# HABSat2_schematic.net
KiCad netlist of a schematic drawn in EasyEDA
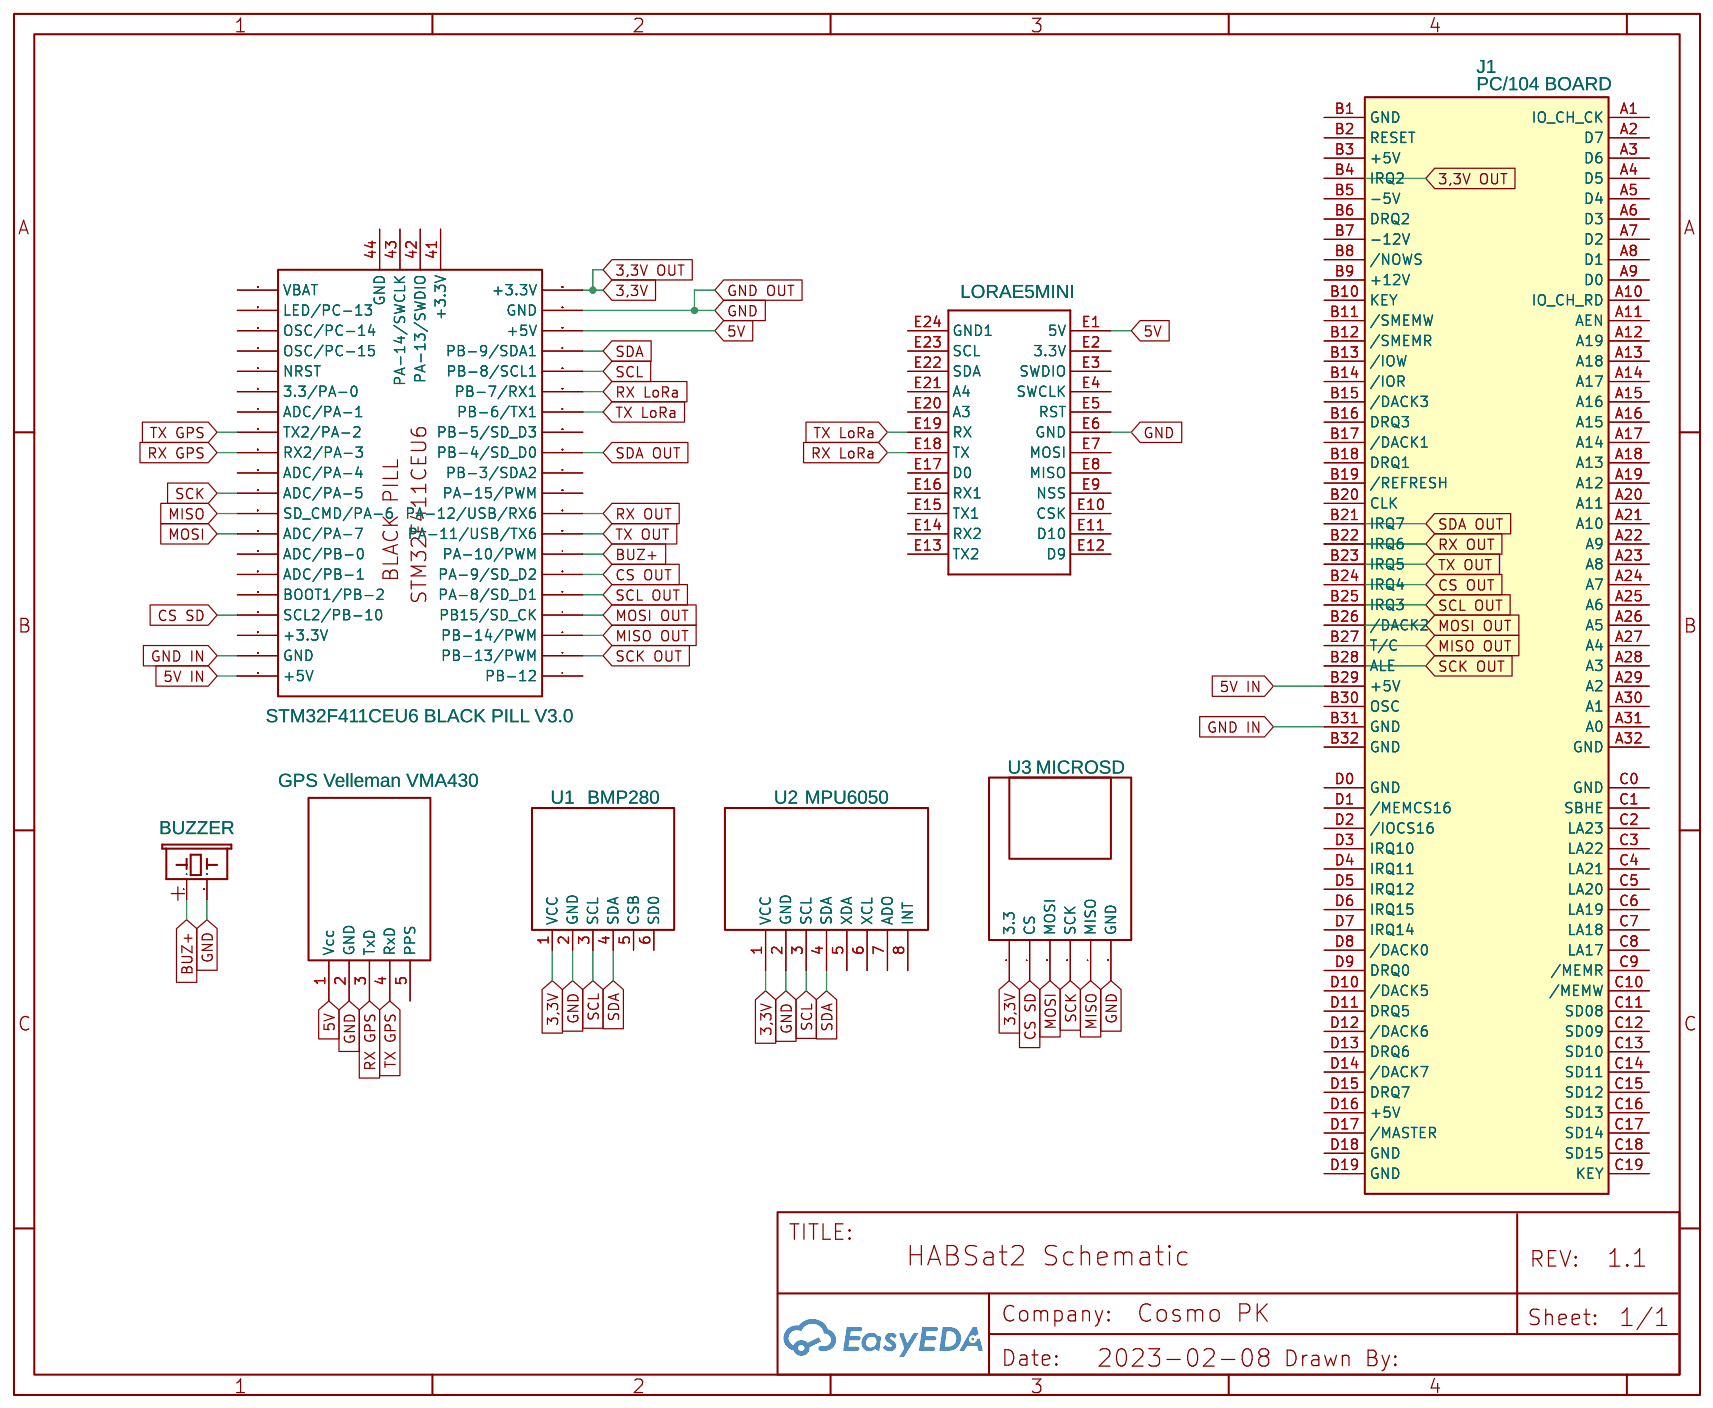
[diagram p0: schematic sheet]

(export (version "E")
  (design (tool "Eeschema 10.0.6"))
  (components
    (comp (ref "1") (value "LORAE5MINI") (libsource (lib "") (part "LORAE5MINI")))
    (comp (ref "J1") (value "PC/104 BOARD") (libsource (lib "") (part "PC/104 BOARD")))
    (comp (ref "SG1") (value "BUZZER") (libsource (lib "") (part "BUZZER KX-12MM")))
    (comp (ref "STM1")
      (value "STM32F411CEU6 BLACK PILL V3.0")
      (libsource (lib "") (part "STM32F411CEU6 BLACK PILL V3.0"))
    )
    (comp (ref "U1")
      (value "BMP280")
      (fields (field (name "BOM_Manufacturer Part") "GY-BMP280"))
      (libsource (lib "") (part "GY-BMP280"))
    )
    (comp (ref "U2") (value "MPU6050") (libsource (lib "") (part "MPU6050")))
    (comp (ref "U3") (value "MICROSD") (libsource (lib "") (part "MICROSD")))
    (comp (ref "VCC")
      (value "GPS Velleman VMA430")
      (fields (field (name "BOM_Manufacturer Part") "VMA430"))
      (libsource (lib "") (part "GPS Velleman VMA430"))
    )
  )
  (nets
    (net (code "1") (name "3,3V") (class "Default")
      (node (ref "J1") (pin "B4") (pinfunction "IRQ2_B4") (pintype "unspecified"))
      (node (ref "STM1") (pin "20") (pinfunction "+3.3V_20") (pintype "unspecified"))
      (node (ref "U1") (pin "1") (pinfunction "VCC_1") (pintype "unspecified"))
      (node (ref "U2") (pin "1") (pinfunction "VCC_1") (pintype "unspecified"))
      (node (ref "U3") (pin "5") (pinfunction "3.3_5") (pintype "unspecified"))
    )
    (net (code "2") (name "5V") (class "Default")
      (node (ref "1") (pin "E1") (pinfunction "5V_E1") (pintype "bidirectional"))
      (node (ref "STM1") (pin "18") (pinfunction "+5V_18") (pintype "unspecified"))
      (node (ref "VCC") (pin "1") (pinfunction "Vcc_1") (pintype "unspecified"))
    )
    (net (code "3") (name "5V IN") (class "Default")
      (node (ref "J1") (pin "B29") (pinfunction "+5V_B29") (pintype "bidirectional"))
      (node (ref "STM1") (pin "40") (pinfunction "+5V_40") (pintype "unspecified"))
    )
    (net (code "4") (name "BUZ+") (class "Default")
      (node (ref "SG1") (pin "1") (pinfunction "1_1") (pintype "unspecified"))
      (node (ref "STM1") (pin "7") (pinfunction "PA-10/PWM_7") (pintype "unspecified"))
    )
    (net (code "5") (name "CS OUT") (class "Default")
      (node (ref "J1") (pin "B24") (pinfunction "IRQ4_B24") (pintype "unspecified"))
      (node (ref "STM1") (pin "6") (pinfunction "PA-9/SD_D2_6") (pintype "unspecified"))
    )
    (net (code "6") (name "CS SD") (class "Default")
      (node (ref "STM1") (pin "37") (pinfunction "SCL2/PB-10_37") (pintype "unspecified"))
      (node (ref "U3") (pin "1") (pinfunction "CS_1") (pintype "unspecified"))
    )
    (net (code "7") (name "GND") (class "Default")
      (node (ref "1") (pin "E6") (pinfunction "GND_E6") (pintype "bidirectional"))
      (node (ref "SG1") (pin "2") (pinfunction "2_2") (pintype "unspecified"))
      (node (ref "STM1") (pin "19") (pinfunction "GND_19") (pintype "unspecified"))
      (node (ref "U1") (pin "2") (pinfunction "GND_2") (pintype "unspecified"))
      (node (ref "U2") (pin "2") (pinfunction "GND_2") (pintype "unspecified"))
      (node (ref "U3") (pin "6") (pinfunction "GND_6") (pintype "unspecified"))
      (node (ref "VCC") (pin "2") (pinfunction "GND_2") (pintype "unspecified"))
    )
    (net (code "8") (name "GND IN") (class "Default")
      (node (ref "J1") (pin "B31") (pinfunction "GND_B31") (pintype "bidirectional"))
      (node (ref "STM1") (pin "39") (pinfunction "GND_39") (pintype "unspecified"))
    )
    (net (code "9") (name "MISO") (class "Default")
      (node (ref "STM1") (pin "32") (pinfunction "SD_CMD/PA-6_32") (pintype "unspecified"))
      (node (ref "U3") (pin "4") (pinfunction "MISO_4") (pintype "unspecified"))
    )
    (net (code "10") (name "MISO OUT") (class "Default")
      (node (ref "J1") (pin "B27") (pinfunction "T/C_B27") (pintype "unspecified"))
      (node (ref "STM1") (pin "3") (pinfunction "PB-14/PWM_3") (pintype "unspecified"))
    )
    (net (code "11") (name "MOSI") (class "Default")
      (node (ref "STM1") (pin "33") (pinfunction "ADC/PA-7_33") (pintype "unspecified"))
      (node (ref "U3") (pin "3") (pinfunction "MOSI_3") (pintype "unspecified"))
    )
    (net (code "12") (name "MOSI OUT") (class "Default")
      (node (ref "J1") (pin "B26") (pinfunction "/DACK2_B26") (pintype "unspecified"))
      (node (ref "STM1") (pin "4") (pinfunction "PB15/SD_CK_4") (pintype "unspecified"))
    )
    (net (code "13") (name "RX GPS") (class "Default")
      (node (ref "STM1") (pin "29") (pinfunction "RX2/PA-3_29") (pintype "unspecified"))
      (node (ref "VCC") (pin "3") (pinfunction "TxD_3") (pintype "unspecified"))
    )
    (net (code "14") (name "RX LoRa") (class "Default")
      (node (ref "1") (pin "E18") (pinfunction "TX_E18") (pintype "bidirectional"))
      (node (ref "STM1") (pin "15") (pinfunction "PB-7/RX1_15") (pintype "unspecified"))
    )
    (net (code "15") (name "RX OUT") (class "Default")
      (node (ref "J1") (pin "B22") (pinfunction "IRQ6_B22") (pintype "unspecified"))
      (node (ref "STM1") (pin "9") (pinfunction "PA-12/USB/RX6_9") (pintype "unspecified"))
    )
    (net (code "16") (name "SCK") (class "Default")
      (node (ref "STM1") (pin "31") (pinfunction "ADC/PA-5_31") (pintype "unspecified"))
      (node (ref "U3") (pin "2") (pinfunction "SCK_2") (pintype "unspecified"))
    )
    (net (code "17") (name "SCK OUT") (class "Default")
      (node (ref "J1") (pin "B28") (pinfunction "ALE_B28") (pintype "output"))
      (node (ref "STM1") (pin "2") (pinfunction "PB-13/PWM_2") (pintype "unspecified"))
    )
    (net (code "18") (name "SCL") (class "Default")
      (node (ref "STM1") (pin "16") (pinfunction "PB-8/SCL1_16") (pintype "unspecified"))
      (node (ref "U1") (pin "3") (pinfunction "SCL_3") (pintype "unspecified"))
      (node (ref "U2") (pin "3") (pinfunction "SCL_3") (pintype "unspecified"))
    )
    (net (code "19") (name "SCL OUT") (class "Default")
      (node (ref "J1") (pin "B25") (pinfunction "IRQ3_B25") (pintype "unspecified"))
      (node (ref "STM1") (pin "5") (pinfunction "PA-8/SD_D1_5") (pintype "unspecified"))
    )
    (net (code "20") (name "SDA") (class "Default")
      (node (ref "STM1") (pin "17") (pinfunction "PB-9/SDA1_17") (pintype "unspecified"))
      (node (ref "U1") (pin "4") (pinfunction "SDA_4") (pintype "unspecified"))
      (node (ref "U2") (pin "4") (pinfunction "SDA_4") (pintype "unspecified"))
    )
    (net (code "21") (name "SDA OUT") (class "Default")
      (node (ref "J1") (pin "B21") (pinfunction "IRQ7_B21") (pintype "unspecified"))
      (node (ref "STM1") (pin "12") (pinfunction "PB-4/SD_D0_12") (pintype "unspecified"))
    )
    (net (code "22") (name "TX GPS") (class "Default")
      (node (ref "STM1") (pin "28") (pinfunction "TX2/PA-2_28") (pintype "unspecified"))
      (node (ref "VCC") (pin "4") (pinfunction "RxD_4") (pintype "unspecified"))
    )
    (net (code "23") (name "TX LoRa") (class "Default")
      (node (ref "1") (pin "E19") (pinfunction "RX_E19") (pintype "bidirectional"))
      (node (ref "STM1") (pin "14") (pinfunction "PB-6/TX1_14") (pintype "unspecified"))
    )
    (net (code "24") (name "TX OUT") (class "Default")
      (node (ref "J1") (pin "B23") (pinfunction "IRQ5_B23") (pintype "unspecified"))
      (node (ref "STM1") (pin "8") (pinfunction "PA-11/USB/TX6_8") (pintype "unspecified"))
    )
    (net (code "25") (name "unconnected-(1-3.3V-PadE2)") (class "Default")
      (node (ref "1") (pin "E2") (pinfunction "3.3V_E2") (pintype "bidirectional"))
    )
    (net (code "26") (name "unconnected-(1-A3-PadE20)") (class "Default")
      (node (ref "1") (pin "E20") (pinfunction "A3_E20") (pintype "bidirectional"))
    )
    (net (code "27") (name "unconnected-(1-A4-PadE21)") (class "Default")
      (node (ref "1") (pin "E21") (pinfunction "A4_E21") (pintype "bidirectional"))
    )
    (net (code "28") (name "unconnected-(1-CSK-PadE10)") (class "Default")
      (node (ref "1") (pin "E10") (pinfunction "CSK_E10") (pintype "bidirectional"))
    )
    (net (code "29") (name "unconnected-(1-D0-PadE17)") (class "Default")
      (node (ref "1") (pin "E17") (pinfunction "D0_E17") (pintype "bidirectional"))
    )
    (net (code "30") (name "unconnected-(1-D9-PadE12)") (class "Default")
      (node (ref "1") (pin "E12") (pinfunction "D9_E12") (pintype "bidirectional"))
    )
    (net (code "31") (name "unconnected-(1-D10-PadE11)") (class "Default")
      (node (ref "1") (pin "E11") (pinfunction "D10_E11") (pintype "bidirectional"))
    )
    (net (code "32") (name "unconnected-(1-GND1-PadE24)") (class "Default")
      (node (ref "1") (pin "E24") (pinfunction "GND1_E24") (pintype "bidirectional"))
    )
    (net (code "33") (name "unconnected-(1-MISO-PadE8)") (class "Default")
      (node (ref "1") (pin "E8") (pinfunction "MISO_E8") (pintype "bidirectional"))
    )
    (net (code "34") (name "unconnected-(1-MOSI-PadE7)") (class "Default")
      (node (ref "1") (pin "E7") (pinfunction "MOSI_E7") (pintype "bidirectional"))
    )
    (net (code "35") (name "unconnected-(1-NSS-PadE9)") (class "Default")
      (node (ref "1") (pin "E9") (pinfunction "NSS_E9") (pintype "bidirectional"))
    )
    (net (code "36") (name "unconnected-(1-RST-PadE5)") (class "Default")
      (node (ref "1") (pin "E5") (pinfunction "RST_E5") (pintype "bidirectional"))
    )
    (net (code "37") (name "unconnected-(1-RX1-PadE16)") (class "Default")
      (node (ref "1") (pin "E16") (pinfunction "RX1_E16") (pintype "bidirectional"))
    )
    (net (code "38") (name "unconnected-(1-RX2-PadE14)") (class "Default")
      (node (ref "1") (pin "E14") (pinfunction "RX2_E14") (pintype "bidirectional"))
    )
    (net (code "39") (name "unconnected-(1-SCL-PadE23)") (class "Default")
      (node (ref "1") (pin "E23") (pinfunction "SCL_E23") (pintype "bidirectional"))
    )
    (net (code "40") (name "unconnected-(1-SDA-PadE22)") (class "Default")
      (node (ref "1") (pin "E22") (pinfunction "SDA_E22") (pintype "bidirectional"))
    )
    (net (code "41") (name "unconnected-(1-SWCLK-PadE4)") (class "Default")
      (node (ref "1") (pin "E4") (pinfunction "SWCLK_E4") (pintype "bidirectional"))
    )
    (net (code "42") (name "unconnected-(1-SWDIO-PadE3)") (class "Default")
      (node (ref "1") (pin "E3") (pinfunction "SWDIO_E3") (pintype "bidirectional"))
    )
    (net (code "43") (name "unconnected-(1-TX1-PadE15)") (class "Default")
      (node (ref "1") (pin "E15") (pinfunction "TX1_E15") (pintype "bidirectional"))
    )
    (net (code "44") (name "unconnected-(1-TX2-PadE13)") (class "Default")
      (node (ref "1") (pin "E13") (pinfunction "TX2_E13") (pintype "bidirectional"))
    )
    (net (code "45") (name "unconnected-(J1-+5V-PadB3)") (class "Default")
      (node (ref "J1") (pin "B3") (pinfunction "+5V_B3") (pintype "bidirectional"))
    )
    (net (code "46") (name "unconnected-(J1-+5V-PadD16)") (class "Default")
      (node (ref "J1") (pin "D16") (pinfunction "+5V_D16") (pintype "bidirectional"))
    )
    (net (code "47") (name "unconnected-(J1-+12V-PadB9)") (class "Default")
      (node (ref "J1") (pin "B9") (pinfunction "+12V_B9") (pintype "bidirectional"))
    )
    (net (code "48") (name "unconnected-(J1--5V-PadB5)") (class "Default")
      (node (ref "J1") (pin "B5") (pinfunction "-5V_B5") (pintype "bidirectional"))
    )
    (net (code "49") (name "unconnected-(J1--12V-PadB7)") (class "Default")
      (node (ref "J1") (pin "B7") (pinfunction "-12V_B7") (pintype "bidirectional"))
    )
    (net (code "50") (name "unconnected-(J1-A0-PadA31)") (class "Default")
      (node (ref "J1") (pin "A31") (pinfunction "A0_A31") (pintype "bidirectional"))
    )
    (net (code "51") (name "unconnected-(J1-A1-PadA30)") (class "Default")
      (node (ref "J1") (pin "A30") (pinfunction "A1_A30") (pintype "bidirectional"))
    )
    (net (code "52") (name "unconnected-(J1-A2-PadA29)") (class "Default")
      (node (ref "J1") (pin "A29") (pinfunction "A2_A29") (pintype "bidirectional"))
    )
    (net (code "53") (name "unconnected-(J1-A3-PadA28)") (class "Default")
      (node (ref "J1") (pin "A28") (pinfunction "A3_A28") (pintype "bidirectional"))
    )
    (net (code "54") (name "unconnected-(J1-A4-PadA27)") (class "Default")
      (node (ref "J1") (pin "A27") (pinfunction "A4_A27") (pintype "bidirectional"))
    )
    (net (code "55") (name "unconnected-(J1-A5-PadA26)") (class "Default")
      (node (ref "J1") (pin "A26") (pinfunction "A5_A26") (pintype "bidirectional"))
    )
    (net (code "56") (name "unconnected-(J1-A6-PadA25)") (class "Default")
      (node (ref "J1") (pin "A25") (pinfunction "A6_A25") (pintype "bidirectional"))
    )
    (net (code "57") (name "unconnected-(J1-A7-PadA24)") (class "Default")
      (node (ref "J1") (pin "A24") (pinfunction "A7_A24") (pintype "bidirectional"))
    )
    (net (code "58") (name "unconnected-(J1-A8-PadA23)") (class "Default")
      (node (ref "J1") (pin "A23") (pinfunction "A8_A23") (pintype "bidirectional"))
    )
    (net (code "59") (name "unconnected-(J1-A9-PadA22)") (class "Default")
      (node (ref "J1") (pin "A22") (pinfunction "A9_A22") (pintype "bidirectional"))
    )
    (net (code "60") (name "unconnected-(J1-A10-PadA21)") (class "Default")
      (node (ref "J1") (pin "A21") (pinfunction "A10_A21") (pintype "bidirectional"))
    )
    (net (code "61") (name "unconnected-(J1-A11-PadA20)") (class "Default")
      (node (ref "J1") (pin "A20") (pinfunction "A11_A20") (pintype "bidirectional"))
    )
    (net (code "62") (name "unconnected-(J1-A12-PadA19)") (class "Default")
      (node (ref "J1") (pin "A19") (pinfunction "A12_A19") (pintype "bidirectional"))
    )
    (net (code "63") (name "unconnected-(J1-A13-PadA18)") (class "Default")
      (node (ref "J1") (pin "A18") (pinfunction "A13_A18") (pintype "bidirectional"))
    )
    (net (code "64") (name "unconnected-(J1-A14-PadA17)") (class "Default")
      (node (ref "J1") (pin "A17") (pinfunction "A14_A17") (pintype "bidirectional"))
    )
    (net (code "65") (name "unconnected-(J1-A15-PadA16)") (class "Default")
      (node (ref "J1") (pin "A16") (pinfunction "A15_A16") (pintype "bidirectional"))
    )
    (net (code "66") (name "unconnected-(J1-A16-PadA15)") (class "Default")
      (node (ref "J1") (pin "A15") (pinfunction "A16_A15") (pintype "bidirectional"))
    )
    (net (code "67") (name "unconnected-(J1-A17-PadA14)") (class "Default")
      (node (ref "J1") (pin "A14") (pinfunction "A17_A14") (pintype "bidirectional"))
    )
    (net (code "68") (name "unconnected-(J1-A18-PadA13)") (class "Default")
      (node (ref "J1") (pin "A13") (pinfunction "A18_A13") (pintype "bidirectional"))
    )
    (net (code "69") (name "unconnected-(J1-A19-PadA12)") (class "Default")
      (node (ref "J1") (pin "A12") (pinfunction "A19_A12") (pintype "bidirectional"))
    )
    (net (code "70") (name "unconnected-(J1-AEN-PadA11)") (class "Default")
      (node (ref "J1") (pin "A11") (pinfunction "AEN_A11") (pintype "output"))
    )
    (net (code "71") (name "unconnected-(J1-CLK-PadB20)") (class "Default")
      (node (ref "J1") (pin "B20") (pinfunction "CLK_B20") (pintype "output"))
    )
    (net (code "72") (name "unconnected-(J1-D0-PadA9)") (class "Default")
      (node (ref "J1") (pin "A9") (pinfunction "D0_A9") (pintype "bidirectional"))
    )
    (net (code "73") (name "unconnected-(J1-D1-PadA8)") (class "Default")
      (node (ref "J1") (pin "A8") (pinfunction "D1_A8") (pintype "bidirectional"))
    )
    (net (code "74") (name "unconnected-(J1-D2-PadA7)") (class "Default")
      (node (ref "J1") (pin "A7") (pinfunction "D2_A7") (pintype "bidirectional"))
    )
    (net (code "75") (name "unconnected-(J1-D3-PadA6)") (class "Default")
      (node (ref "J1") (pin "A6") (pinfunction "D3_A6") (pintype "bidirectional"))
    )
    (net (code "76") (name "unconnected-(J1-D4-PadA5)") (class "Default")
      (node (ref "J1") (pin "A5") (pinfunction "D4_A5") (pintype "bidirectional"))
    )
    (net (code "77") (name "unconnected-(J1-D5-PadA4)") (class "Default")
      (node (ref "J1") (pin "A4") (pinfunction "D5_A4") (pintype "bidirectional"))
    )
    (net (code "78") (name "unconnected-(J1-D6-PadA3)") (class "Default")
      (node (ref "J1") (pin "A3") (pinfunction "D6_A3") (pintype "bidirectional"))
    )
    (net (code "79") (name "unconnected-(J1-D7-PadA2)") (class "Default")
      (node (ref "J1") (pin "A2") (pinfunction "D7_A2") (pintype "bidirectional"))
    )
    (net (code "80") (name "unconnected-(J1-DRQ0-PadD9)") (class "Default")
      (node (ref "J1") (pin "D9") (pinfunction "DRQ0_D9") (pintype "unspecified"))
    )
    (net (code "81") (name "unconnected-(J1-DRQ1-PadB18)") (class "Default")
      (node (ref "J1") (pin "B18") (pinfunction "DRQ1_B18") (pintype "unspecified"))
    )
    (net (code "82") (name "unconnected-(J1-DRQ2-PadB6)") (class "Default")
      (node (ref "J1") (pin "B6") (pinfunction "DRQ2_B6") (pintype "unspecified"))
    )
    (net (code "83") (name "unconnected-(J1-DRQ3-PadB16)") (class "Default")
      (node (ref "J1") (pin "B16") (pinfunction "DRQ3_B16") (pintype "unspecified"))
    )
    (net (code "84") (name "unconnected-(J1-DRQ5-PadD11)") (class "Default")
      (node (ref "J1") (pin "D11") (pinfunction "DRQ5_D11") (pintype "unspecified"))
    )
    (net (code "85") (name "unconnected-(J1-DRQ6-PadD13)") (class "Default")
      (node (ref "J1") (pin "D13") (pinfunction "DRQ6_D13") (pintype "unspecified"))
    )
    (net (code "86") (name "unconnected-(J1-DRQ7-PadD15)") (class "Default")
      (node (ref "J1") (pin "D15") (pinfunction "DRQ7_D15") (pintype "unspecified"))
    )
    (net (code "87") (name "unconnected-(J1-GND-PadA32)") (class "Default")
      (node (ref "J1") (pin "A32") (pinfunction "GND_A32") (pintype "bidirectional"))
    )
    (net (code "88") (name "unconnected-(J1-GND-PadB1)") (class "Default")
      (node (ref "J1") (pin "B1") (pinfunction "GND_B1") (pintype "bidirectional"))
    )
    (net (code "89") (name "unconnected-(J1-GND-PadB32)") (class "Default")
      (node (ref "J1") (pin "B32") (pinfunction "GND_B32") (pintype "bidirectional"))
    )
    (net (code "90") (name "unconnected-(J1-GND-PadC0)") (class "Default")
      (node (ref "J1") (pin "C0") (pinfunction "GND_C0") (pintype "unspecified"))
    )
    (net (code "91") (name "unconnected-(J1-GND-PadD0)") (class "Default")
      (node (ref "J1") (pin "D0") (pinfunction "GND_D0") (pintype "unspecified"))
    )
    (net (code "92") (name "unconnected-(J1-GND-PadD18)") (class "Default")
      (node (ref "J1") (pin "D18") (pinfunction "GND_D18") (pintype "bidirectional"))
    )
    (net (code "93") (name "unconnected-(J1-GND-PadD19)") (class "Default")
      (node (ref "J1") (pin "D19") (pinfunction "GND_D19") (pintype "bidirectional"))
    )
    (net (code "94") (name "unconnected-(J1-IO_CH_CK-PadA1)") (class "Default")
      (node (ref "J1") (pin "A1") (pinfunction "IO_CH_CK_A1") (pintype "unspecified"))
    )
    (net (code "95") (name "unconnected-(J1-IO_CH_RD-PadA10)") (class "Default")
      (node (ref "J1") (pin "A10") (pinfunction "IO_CH_RD_A10") (pintype "unspecified"))
    )
    (net (code "96") (name "unconnected-(J1-IRQ10-PadD3)") (class "Default")
      (node (ref "J1") (pin "D3") (pinfunction "IRQ10_D3") (pintype "unspecified"))
    )
    (net (code "97") (name "unconnected-(J1-IRQ11-PadD4)") (class "Default")
      (node (ref "J1") (pin "D4") (pinfunction "IRQ11_D4") (pintype "unspecified"))
    )
    (net (code "98") (name "unconnected-(J1-IRQ12-PadD5)") (class "Default")
      (node (ref "J1") (pin "D5") (pinfunction "IRQ12_D5") (pintype "unspecified"))
    )
    (net (code "99") (name "unconnected-(J1-IRQ14-PadD7)") (class "Default")
      (node (ref "J1") (pin "D7") (pinfunction "IRQ14_D7") (pintype "unspecified"))
    )
    (net (code "100") (name "unconnected-(J1-IRQ15-PadD6)") (class "Default")
      (node (ref "J1") (pin "D6") (pinfunction "IRQ15_D6") (pintype "unspecified"))
    )
    (net (code "101") (name "unconnected-(J1-KEY-PadB10)") (class "Default")
      (node (ref "J1") (pin "B10") (pinfunction "KEY_B10") (pintype "bidirectional"))
    )
    (net (code "102") (name "unconnected-(J1-KEY-PadC19)") (class "Default")
      (node (ref "J1") (pin "C19") (pinfunction "KEY_C19") (pintype "bidirectional"))
    )
    (net (code "103") (name "unconnected-(J1-LA17-PadC8)") (class "Default")
      (node (ref "J1") (pin "C8") (pinfunction "LA17_C8") (pintype "unspecified"))
    )
    (net (code "104") (name "unconnected-(J1-LA18-PadC7)") (class "Default")
      (node (ref "J1") (pin "C7") (pinfunction "LA18_C7") (pintype "unspecified"))
    )
    (net (code "105") (name "unconnected-(J1-LA19-PadC6)") (class "Default")
      (node (ref "J1") (pin "C6") (pinfunction "LA19_C6") (pintype "unspecified"))
    )
    (net (code "106") (name "unconnected-(J1-LA20-PadC5)") (class "Default")
      (node (ref "J1") (pin "C5") (pinfunction "LA20_C5") (pintype "unspecified"))
    )
    (net (code "107") (name "unconnected-(J1-LA21-PadC4)") (class "Default")
      (node (ref "J1") (pin "C4") (pinfunction "LA21_C4") (pintype "unspecified"))
    )
    (net (code "108") (name "unconnected-(J1-LA22-PadC3)") (class "Default")
      (node (ref "J1") (pin "C3") (pinfunction "LA22_C3") (pintype "unspecified"))
    )
    (net (code "109") (name "unconnected-(J1-LA23-PadC2)") (class "Default")
      (node (ref "J1") (pin "C2") (pinfunction "LA23_C2") (pintype "unspecified"))
    )
    (net (code "110") (name "unconnected-(J1-OSC-PadB30)") (class "Default")
      (node (ref "J1") (pin "B30") (pinfunction "OSC_B30") (pintype "output"))
    )
    (net (code "111") (name "unconnected-(J1-RESET-PadB2)") (class "Default")
      (node (ref "J1") (pin "B2") (pinfunction "RESET_B2") (pintype "output"))
    )
    (net (code "112") (name "unconnected-(J1-SBHE-PadC1)") (class "Default")
      (node (ref "J1") (pin "C1") (pinfunction "SBHE_C1") (pintype "unspecified"))
    )
    (net (code "113") (name "unconnected-(J1-SD08-PadC11)") (class "Default")
      (node (ref "J1") (pin "C11") (pinfunction "SD08_C11") (pintype "bidirectional"))
    )
    (net (code "114") (name "unconnected-(J1-SD09-PadC12)") (class "Default")
      (node (ref "J1") (pin "C12") (pinfunction "SD09_C12") (pintype "bidirectional"))
    )
    (net (code "115") (name "unconnected-(J1-SD10-PadC13)") (class "Default")
      (node (ref "J1") (pin "C13") (pinfunction "SD10_C13") (pintype "bidirectional"))
    )
    (net (code "116") (name "unconnected-(J1-SD11-PadC14)") (class "Default")
      (node (ref "J1") (pin "C14") (pinfunction "SD11_C14") (pintype "bidirectional"))
    )
    (net (code "117") (name "unconnected-(J1-SD12-PadC15)") (class "Default")
      (node (ref "J1") (pin "C15") (pinfunction "SD12_C15") (pintype "bidirectional"))
    )
    (net (code "118") (name "unconnected-(J1-SD13-PadC16)") (class "Default")
      (node (ref "J1") (pin "C16") (pinfunction "SD13_C16") (pintype "bidirectional"))
    )
    (net (code "119") (name "unconnected-(J1-SD14-PadC17)") (class "Default")
      (node (ref "J1") (pin "C17") (pinfunction "SD14_C17") (pintype "bidirectional"))
    )
    (net (code "120") (name "unconnected-(J1-SD15-PadC18)") (class "Default")
      (node (ref "J1") (pin "C18") (pinfunction "SD15_C18") (pintype "bidirectional"))
    )
    (net (code "121") (name "unconnected-(J1-{slash}DACK0-PadD8)") (class "Default")
      (node (ref "J1") (pin "D8") (pinfunction "/DACK0_D8") (pintype "output"))
    )
    (net (code "122") (name "unconnected-(J1-{slash}DACK1-PadB17)") (class "Default")
      (node (ref "J1") (pin "B17") (pinfunction "/DACK1_B17") (pintype "unspecified"))
    )
    (net (code "123") (name "unconnected-(J1-{slash}DACK3-PadB15)") (class "Default")
      (node (ref "J1") (pin "B15") (pinfunction "/DACK3_B15") (pintype "unspecified"))
    )
    (net (code "124") (name "unconnected-(J1-{slash}DACK5-PadD10)") (class "Default")
      (node (ref "J1") (pin "D10") (pinfunction "/DACK5_D10") (pintype "output"))
    )
    (net (code "125") (name "unconnected-(J1-{slash}DACK6-PadD12)") (class "Default")
      (node (ref "J1") (pin "D12") (pinfunction "/DACK6_D12") (pintype "output"))
    )
    (net (code "126") (name "unconnected-(J1-{slash}DACK7-PadD14)") (class "Default")
      (node (ref "J1") (pin "D14") (pinfunction "/DACK7_D14") (pintype "output"))
    )
    (net (code "127") (name "unconnected-(J1-{slash}IOCS16-PadD2)") (class "Default")
      (node (ref "J1") (pin "D2") (pinfunction "/IOCS16_D2") (pintype "unspecified"))
    )
    (net (code "128") (name "unconnected-(J1-{slash}IOR-PadB14)") (class "Default")
      (node (ref "J1") (pin "B14") (pinfunction "/IOR_B14") (pintype "output"))
    )
    (net (code "129") (name "unconnected-(J1-{slash}IOW-PadB13)") (class "Default")
      (node (ref "J1") (pin "B13") (pinfunction "/IOW_B13") (pintype "output"))
    )
    (net (code "130") (name "unconnected-(J1-{slash}MASTER-PadD17)") (class "Default")
      (node (ref "J1") (pin "D17") (pinfunction "/MASTER_D17") (pintype "unspecified"))
    )
    (net (code "131") (name "unconnected-(J1-{slash}MEMCS16-PadD1)") (class "Default")
      (node (ref "J1") (pin "D1") (pinfunction "/MEMCS16_D1") (pintype "unspecified"))
    )
    (net (code "132") (name "unconnected-(J1-{slash}MEMR-PadC9)") (class "Default")
      (node (ref "J1") (pin "C9") (pinfunction "/MEMR_C9") (pintype "output"))
    )
    (net (code "133") (name "unconnected-(J1-{slash}MEMW-PadC10)") (class "Default")
      (node (ref "J1") (pin "C10") (pinfunction "/MEMW_C10") (pintype "output"))
    )
    (net (code "134") (name "unconnected-(J1-{slash}NOWS-PadB8)") (class "Default")
      (node (ref "J1") (pin "B8") (pinfunction "/NOWS_B8") (pintype "unspecified"))
    )
    (net (code "135") (name "unconnected-(J1-{slash}REFRESH-PadB19)") (class "Default")
      (node (ref "J1") (pin "B19") (pinfunction "/REFRESH_B19") (pintype "unspecified"))
    )
    (net (code "136") (name "unconnected-(J1-{slash}SMEMR-PadB12)") (class "Default")
      (node (ref "J1") (pin "B12") (pinfunction "/SMEMR_B12") (pintype "output"))
    )
    (net (code "137") (name "unconnected-(J1-{slash}SMEMW-PadB11)") (class "Default")
      (node (ref "J1") (pin "B11") (pinfunction "/SMEMW_B11") (pintype "output"))
    )
    (net (code "138") (name "unconnected-(STM1-+3.3V-Pad38)") (class "Default")
      (node (ref "STM1") (pin "38") (pinfunction "+3.3V_38") (pintype "unspecified"))
    )
    (net (code "139") (name "unconnected-(STM1-+3.3V-Pad41)") (class "Default")
      (node (ref "STM1") (pin "41") (pinfunction "+3.3V_41") (pintype "unspecified"))
    )
    (net (code "140") (name "unconnected-(STM1-3.3{slash}PA-0-Pad26)") (class "Default")
      (node (ref "STM1") (pin "26") (pinfunction "3.3/PA-0_26") (pintype "unspecified"))
    )
    (net (code "141") (name "unconnected-(STM1-ADC{slash}PA-1-Pad27)") (class "Default")
      (node (ref "STM1") (pin "27") (pinfunction "ADC/PA-1_27") (pintype "unspecified"))
    )
    (net (code "142") (name "unconnected-(STM1-ADC{slash}PA-4-Pad30)") (class "Default")
      (node (ref "STM1") (pin "30") (pinfunction "ADC/PA-4_30") (pintype "unspecified"))
    )
    (net (code "143") (name "unconnected-(STM1-ADC{slash}PB-0-Pad34)") (class "Default")
      (node (ref "STM1") (pin "34") (pinfunction "ADC/PB-0_34") (pintype "unspecified"))
    )
    (net (code "144") (name "unconnected-(STM1-ADC{slash}PB-1-Pad35)") (class "Default")
      (node (ref "STM1") (pin "35") (pinfunction "ADC/PB-1_35") (pintype "unspecified"))
    )
    (net (code "145") (name "unconnected-(STM1-BOOT1{slash}PB-2-Pad36)") (class "Default")
      (node (ref "STM1") (pin "36") (pinfunction "BOOT1/PB-2_36") (pintype "unspecified"))
    )
    (net (code "146") (name "unconnected-(STM1-GND-Pad44)") (class "Default")
      (node (ref "STM1") (pin "44") (pinfunction "GND_44") (pintype "unspecified"))
    )
    (net (code "147") (name "unconnected-(STM1-LED{slash}PC-13-Pad22)") (class "Default")
      (node (ref "STM1") (pin "22") (pinfunction "LED/PC-13_22") (pintype "unspecified"))
    )
    (net (code "148") (name "unconnected-(STM1-NRST-Pad25)") (class "Default")
      (node (ref "STM1") (pin "25") (pinfunction "NRST_25") (pintype "unspecified"))
    )
    (net (code "149") (name "unconnected-(STM1-OSC{slash}PC-14-Pad23)") (class "Default")
      (node (ref "STM1") (pin "23") (pinfunction "OSC/PC-14_23") (pintype "unspecified"))
    )
    (net (code "150") (name "unconnected-(STM1-OSC{slash}PC-15-Pad24)") (class "Default")
      (node (ref "STM1") (pin "24") (pinfunction "OSC/PC-15_24") (pintype "unspecified"))
    )
    (net (code "151") (name "unconnected-(STM1-PA-13{slash}SWDIO-Pad42)") (class "Default")
      (node (ref "STM1") (pin "42") (pinfunction "PA-13/SWDIO_42") (pintype "unspecified"))
    )
    (net (code "152") (name "unconnected-(STM1-PA-14{slash}SWCLK-Pad43)") (class "Default")
      (node (ref "STM1") (pin "43") (pinfunction "PA-14/SWCLK_43") (pintype "unspecified"))
    )
    (net (code "153") (name "unconnected-(STM1-PA-15{slash}PWM-Pad10)") (class "Default")
      (node (ref "STM1") (pin "10") (pinfunction "PA-15/PWM_10") (pintype "unspecified"))
    )
    (net (code "154") (name "unconnected-(STM1-PB-3{slash}SDA2-Pad11)") (class "Default")
      (node (ref "STM1") (pin "11") (pinfunction "PB-3/SDA2_11") (pintype "unspecified"))
    )
    (net (code "155") (name "unconnected-(STM1-PB-5{slash}SD_D3-Pad13)") (class "Default")
      (node (ref "STM1") (pin "13") (pinfunction "PB-5/SD_D3_13") (pintype "unspecified"))
    )
    (net (code "156") (name "unconnected-(STM1-PB-12-Pad1)") (class "Default")
      (node (ref "STM1") (pin "1") (pinfunction "PB-12_1") (pintype "unspecified"))
    )
    (net (code "157") (name "unconnected-(STM1-VBAT-Pad21)") (class "Default")
      (node (ref "STM1") (pin "21") (pinfunction "VBAT_21") (pintype "unspecified"))
    )
    (net (code "158") (name "unconnected-(U1-CSB-Pad5)") (class "Default")
      (node (ref "U1") (pin "5") (pinfunction "CSB_5") (pintype "unspecified"))
    )
    (net (code "159") (name "unconnected-(U1-SD0-Pad6)") (class "Default")
      (node (ref "U1") (pin "6") (pinfunction "SD0_6") (pintype "unspecified"))
    )
    (net (code "160") (name "unconnected-(U2-ADO-Pad7)") (class "Default")
      (node (ref "U2") (pin "7") (pinfunction "ADO_7") (pintype "unspecified"))
    )
    (net (code "161") (name "unconnected-(U2-INT-Pad8)") (class "Default")
      (node (ref "U2") (pin "8") (pinfunction "INT_8") (pintype "unspecified"))
    )
    (net (code "162") (name "unconnected-(U2-XCL-Pad6)") (class "Default")
      (node (ref "U2") (pin "6") (pinfunction "XCL_6") (pintype "unspecified"))
    )
    (net (code "163") (name "unconnected-(U2-XDA-Pad5)") (class "Default")
      (node (ref "U2") (pin "5") (pinfunction "XDA_5") (pintype "unspecified"))
    )
    (net (code "164") (name "unconnected-(VCC-PPS-Pad5)") (class "Default")
      (node (ref "VCC") (pin "5") (pinfunction "PPS_5") (pintype "unspecified"))
    )
  )
)
